# SCH_webLed_2024-11-11.net
KiCad netlist of a schematic drawn in EasyEDA
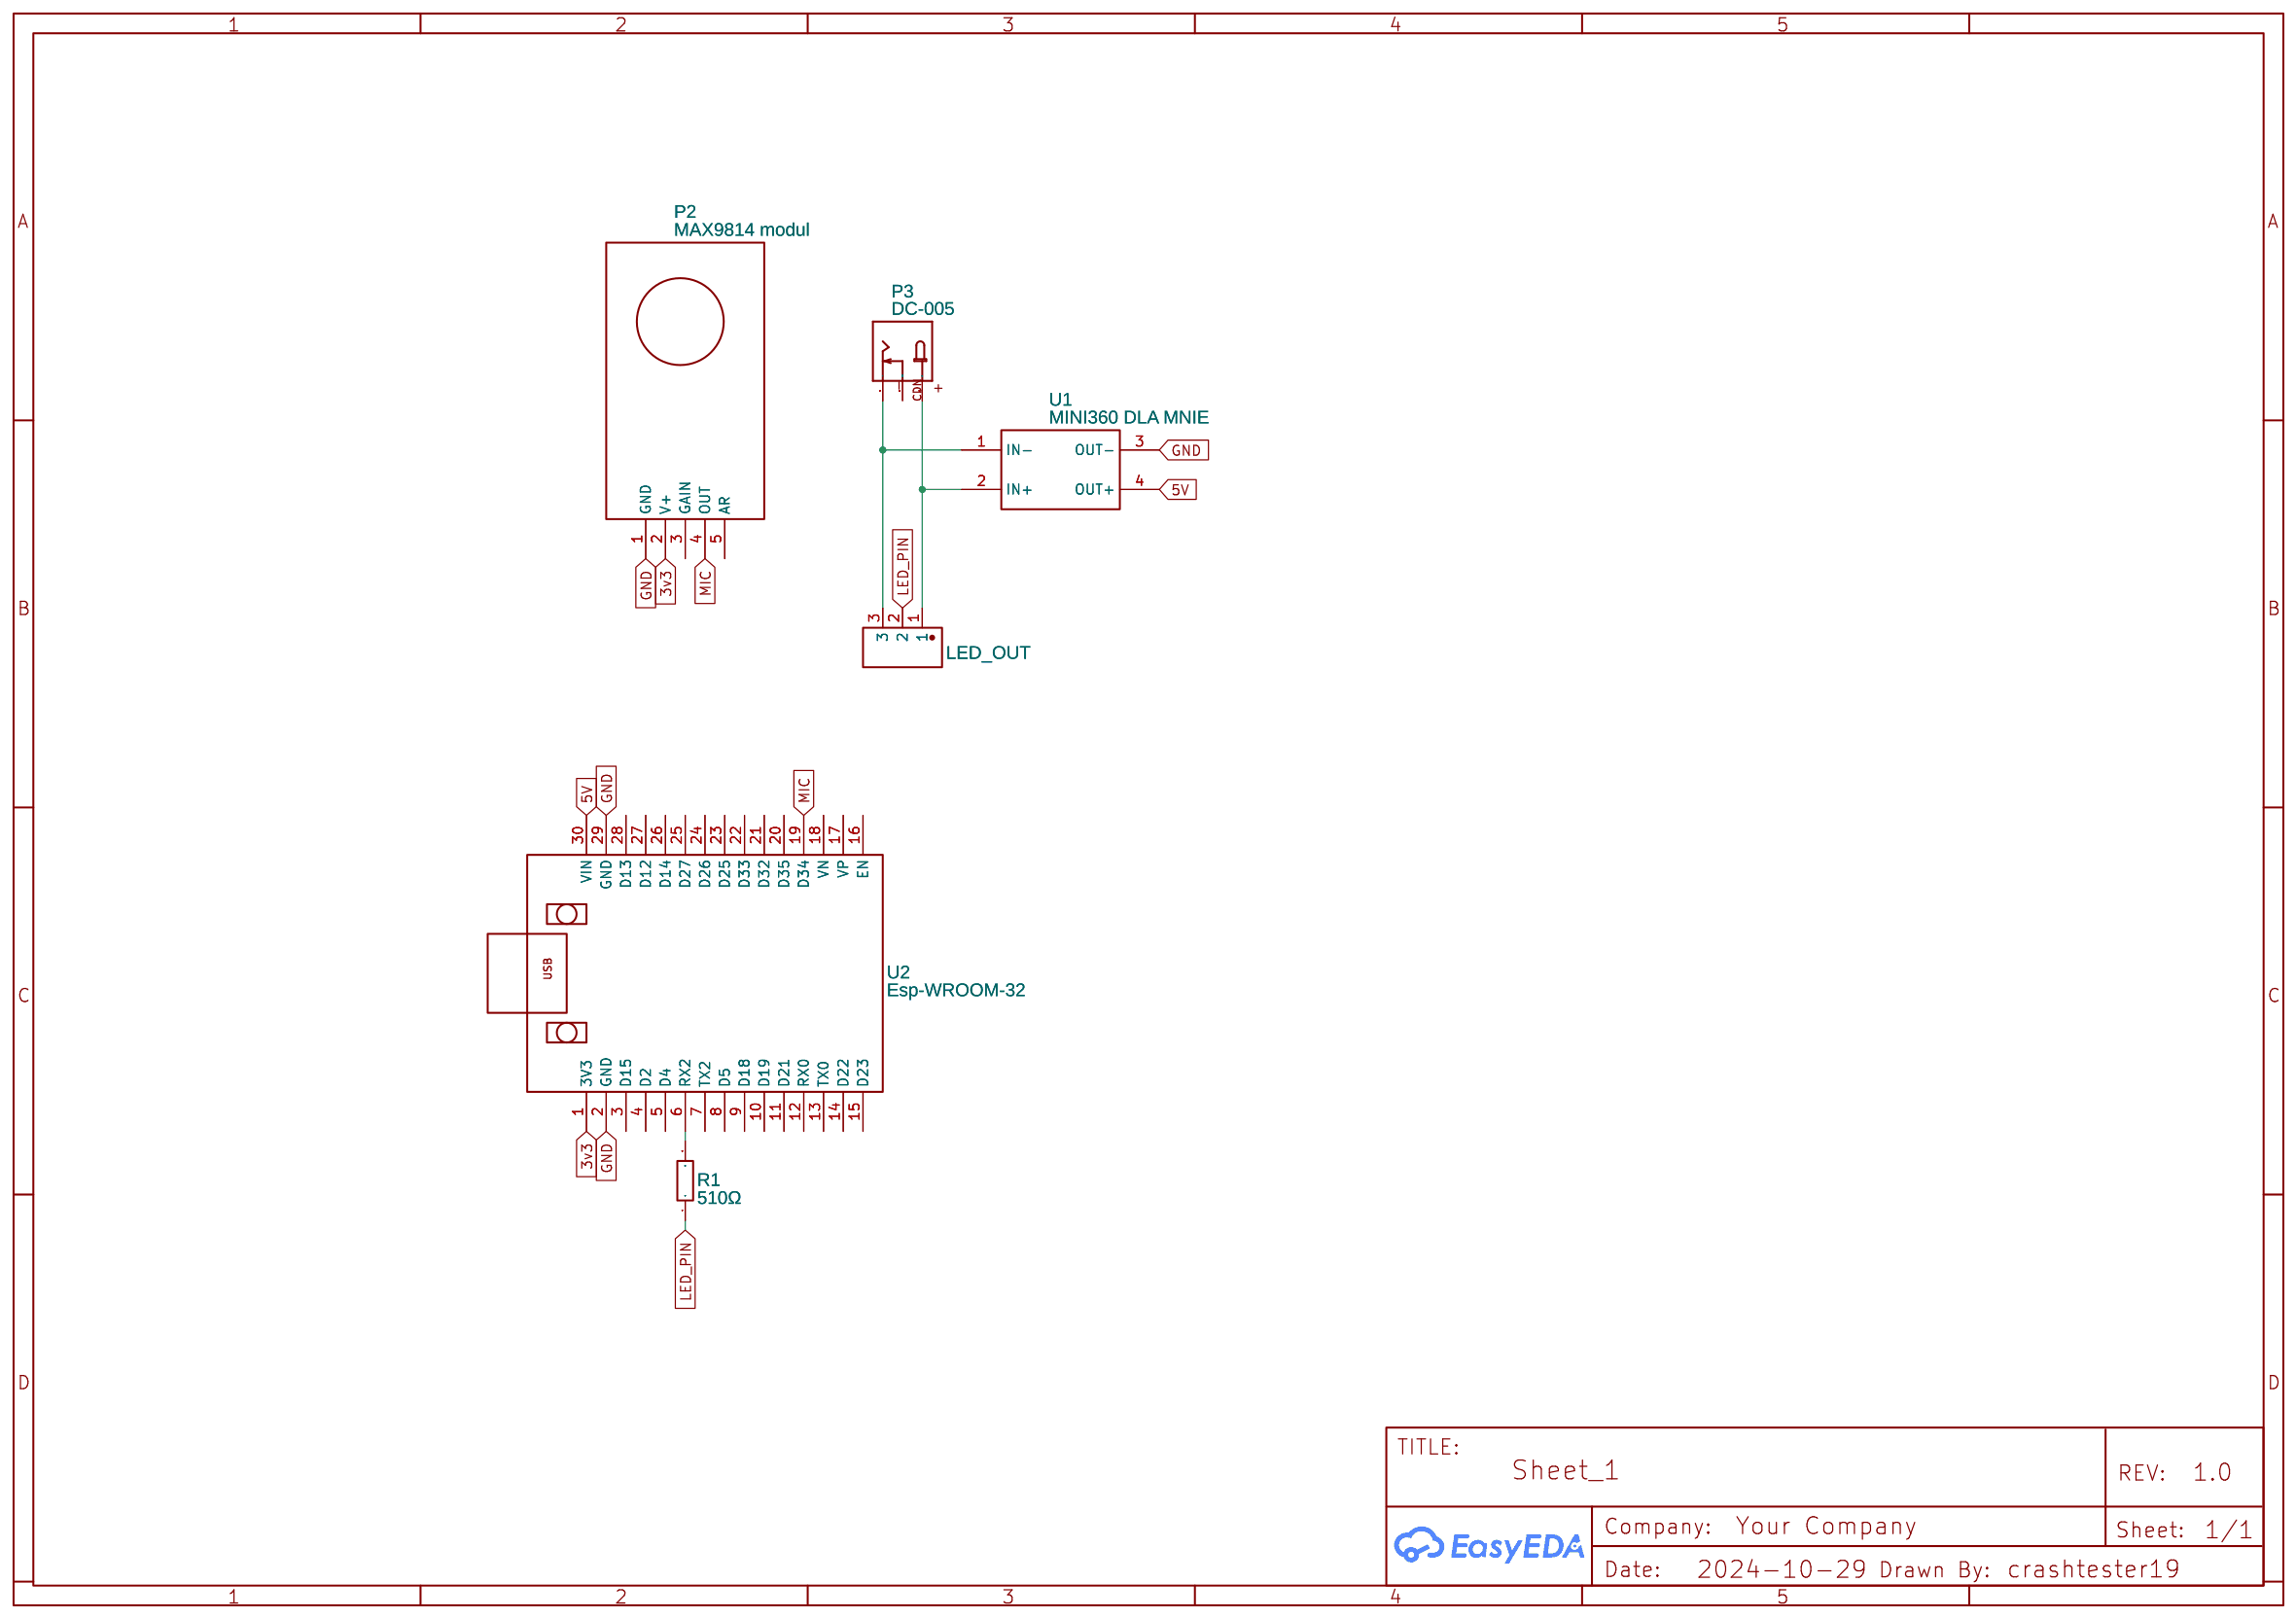
[diagram p0: schematic sheet]

(export (version "E")
  (design (tool "Eeschema 10.0.6"))
  (components
    (comp (ref "H2")
      (value "LED_OUT")
      (fields (field (name "Manufacturer Part") "PZ254R-11-03P") (field (name "Manufacturer") "XFCN"))
      (libsource (lib "") (part "PZ254R-11-03P"))
    )
    (comp (ref "P2") (value "MAX9814 modul") (libsource (lib "") (part "MAX9814 modul")))
    (comp (ref "P3") (value "DC-005") (libsource (lib "") (part "DC-005")))
    (comp (ref "R1")
      (value "510Ω")
      (fields (field (name "Manufacturer Part") "CF3WS-510Ω±5% T") (field (name "Manufacturer") "CCO(千志电子)"))
      (libsource (lib "") (part "CF3WS-510Ω±5% T"))
    )
    (comp (ref "U1")
      (value "MINI360 DLA MNIE")
      (fields (field (name "Manufacturer Part") "Mini360"))
      (libsource (lib "") (part "MINI360BUCK_SMALL"))
    )
    (comp (ref "U2") (value "Esp-WROOM-32") (libsource (lib "") (part "Esp32-WROOM-30 Dev board")))
  )
  (nets
    (net (code "1") (name "3v3") (class "Default")
      (node (ref "P2") (pin "2") (pinfunction "V+_2") (pintype "unspecified"))
      (node (ref "U2") (pin "1") (pinfunction "3V3_1") (pintype "unspecified"))
    )
    (net (code "2") (name "5V") (class "Default")
      (node (ref "U1") (pin "4") (pinfunction "OUT+_4") (pintype "unspecified"))
      (node (ref "U2") (pin "30") (pinfunction "VIN_30") (pintype "unspecified"))
    )
    (net (code "3") (name "GND") (class "Default")
      (node (ref "P2") (pin "1") (pinfunction "GND_1") (pintype "unspecified"))
      (node (ref "U1") (pin "3") (pinfunction "OUT-_3") (pintype "unspecified"))
      (node (ref "U2") (pin "2") (pinfunction "GND_2") (pintype "unspecified"))
      (node (ref "U2") (pin "29") (pinfunction "GND_29") (pintype "unspecified"))
    )
    (net (code "4") (name "LED_PIN") (class "Default")
      (node (ref "H2") (pin "2") (pinfunction "2_2") (pintype "unspecified"))
      (node (ref "R1") (pin "1") (pinfunction "1_1") (pintype "unspecified"))
    )
    (net (code "5") (name "MIC") (class "Default")
      (node (ref "P2") (pin "4") (pinfunction "OUT_4") (pintype "unspecified"))
      (node (ref "U2") (pin "19") (pinfunction "D34_19") (pintype "unspecified"))
    )
    (net (code "6") (name "Net-(P3-+)") (class "Default")
      (node (ref "H2") (pin "1") (pinfunction "1_1") (pintype "unspecified"))
      (node (ref "P3") (pin "1") (pinfunction "+_1") (pintype "unspecified"))
      (node (ref "U1") (pin "2") (pinfunction "IN+_2") (pintype "unspecified"))
    )
    (net (code "7") (name "Net-(P3--)") (class "Default")
      (node (ref "H2") (pin "3") (pinfunction "3_3") (pintype "unspecified"))
      (node (ref "P3") (pin "2") (pinfunction "-_2") (pintype "unspecified"))
      (node (ref "U1") (pin "1") (pinfunction "IN-_1") (pintype "unspecified"))
    )
    (net (code "8") (name "Net-(U2-RX2)") (class "Default")
      (node (ref "R1") (pin "2") (pinfunction "2_2") (pintype "unspecified"))
      (node (ref "U2") (pin "6") (pinfunction "RX2_6") (pintype "unspecified"))
    )
    (net (code "9") (name "unconnected-(P2-AR-Pad5)") (class "Default")
      (node (ref "P2") (pin "5") (pinfunction "AR_5") (pintype "unspecified"))
    )
    (net (code "10") (name "unconnected-(P2-GAIN-Pad3)") (class "Default")
      (node (ref "P2") (pin "3") (pinfunction "GAIN_3") (pintype "unspecified"))
    )
    (net (code "11") (name "unconnected-(P3-CDN-Pad3)") (class "Default")
      (node (ref "P3") (pin "3") (pinfunction "CDN_3") (pintype "unspecified"))
    )
    (net (code "12") (name "unconnected-(U2-D2-Pad4)") (class "Default")
      (node (ref "U2") (pin "4") (pinfunction "D2_4") (pintype "unspecified"))
    )
    (net (code "13") (name "unconnected-(U2-D4-Pad5)") (class "Default")
      (node (ref "U2") (pin "5") (pinfunction "D4_5") (pintype "unspecified"))
    )
    (net (code "14") (name "unconnected-(U2-D5-Pad8)") (class "Default")
      (node (ref "U2") (pin "8") (pinfunction "D5_8") (pintype "unspecified"))
    )
    (net (code "15") (name "unconnected-(U2-D12-Pad27)") (class "Default")
      (node (ref "U2") (pin "27") (pinfunction "D12_27") (pintype "unspecified"))
    )
    (net (code "16") (name "unconnected-(U2-D13-Pad28)") (class "Default")
      (node (ref "U2") (pin "28") (pinfunction "D13_28") (pintype "unspecified"))
    )
    (net (code "17") (name "unconnected-(U2-D14-Pad26)") (class "Default")
      (node (ref "U2") (pin "26") (pinfunction "D14_26") (pintype "unspecified"))
    )
    (net (code "18") (name "unconnected-(U2-D15-Pad3)") (class "Default")
      (node (ref "U2") (pin "3") (pinfunction "D15_3") (pintype "unspecified"))
    )
    (net (code "19") (name "unconnected-(U2-D18-Pad9)") (class "Default")
      (node (ref "U2") (pin "9") (pinfunction "D18_9") (pintype "unspecified"))
    )
    (net (code "20") (name "unconnected-(U2-D19-Pad10)") (class "Default")
      (node (ref "U2") (pin "10") (pinfunction "D19_10") (pintype "unspecified"))
    )
    (net (code "21") (name "unconnected-(U2-D21-Pad11)") (class "Default")
      (node (ref "U2") (pin "11") (pinfunction "D21_11") (pintype "unspecified"))
    )
    (net (code "22") (name "unconnected-(U2-D22-Pad14)") (class "Default")
      (node (ref "U2") (pin "14") (pinfunction "D22_14") (pintype "unspecified"))
    )
    (net (code "23") (name "unconnected-(U2-D23-Pad15)") (class "Default")
      (node (ref "U2") (pin "15") (pinfunction "D23_15") (pintype "unspecified"))
    )
    (net (code "24") (name "unconnected-(U2-D25-Pad23)") (class "Default")
      (node (ref "U2") (pin "23") (pinfunction "D25_23") (pintype "unspecified"))
    )
    (net (code "25") (name "unconnected-(U2-D26-Pad24)") (class "Default")
      (node (ref "U2") (pin "24") (pinfunction "D26_24") (pintype "unspecified"))
    )
    (net (code "26") (name "unconnected-(U2-D27-Pad25)") (class "Default")
      (node (ref "U2") (pin "25") (pinfunction "D27_25") (pintype "unspecified"))
    )
    (net (code "27") (name "unconnected-(U2-D32-Pad21)") (class "Default")
      (node (ref "U2") (pin "21") (pinfunction "D32_21") (pintype "unspecified"))
    )
    (net (code "28") (name "unconnected-(U2-D33-Pad22)") (class "Default")
      (node (ref "U2") (pin "22") (pinfunction "D33_22") (pintype "unspecified"))
    )
    (net (code "29") (name "unconnected-(U2-D35-Pad20)") (class "Default")
      (node (ref "U2") (pin "20") (pinfunction "D35_20") (pintype "unspecified"))
    )
    (net (code "30") (name "unconnected-(U2-EN-Pad16)") (class "Default")
      (node (ref "U2") (pin "16") (pinfunction "EN_16") (pintype "unspecified"))
    )
    (net (code "31") (name "unconnected-(U2-RX0-Pad12)") (class "Default")
      (node (ref "U2") (pin "12") (pinfunction "RX0_12") (pintype "unspecified"))
    )
    (net (code "32") (name "unconnected-(U2-TX0-Pad13)") (class "Default")
      (node (ref "U2") (pin "13") (pinfunction "TX0_13") (pintype "unspecified"))
    )
    (net (code "33") (name "unconnected-(U2-TX2-Pad7)") (class "Default")
      (node (ref "U2") (pin "7") (pinfunction "TX2_7") (pintype "unspecified"))
    )
    (net (code "34") (name "unconnected-(U2-VN-Pad18)") (class "Default")
      (node (ref "U2") (pin "18") (pinfunction "VN_18") (pintype "unspecified"))
    )
    (net (code "35") (name "unconnected-(U2-VP-Pad17)") (class "Default")
      (node (ref "U2") (pin "17") (pinfunction "VP_17") (pintype "unspecified"))
    )
  )
)
